# Power-PCB.net
KiCad netlist of a schematic drawn in EAGLE
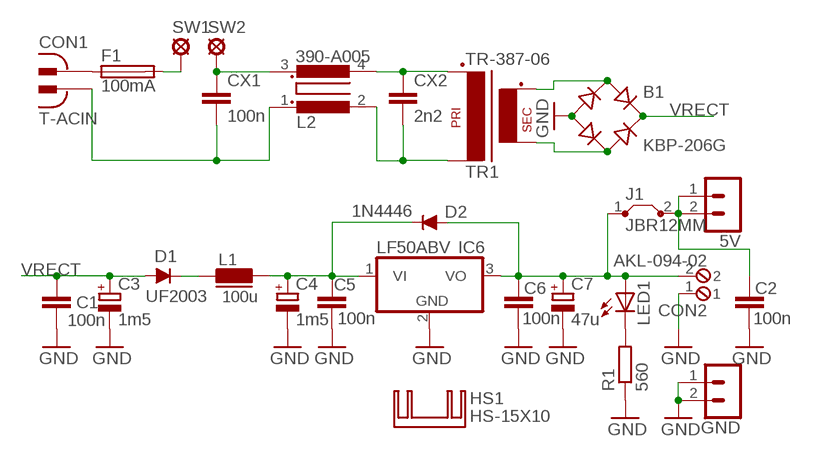
[diagram p0: schematic, sheet 1]

(export (version "E")
  (design (tool "Eeschema 10.0.6"))
  (components
    (comp (ref "5V")
      (value "MA02-1")
      (footprint "eagle-import:MA02-1")
      (libsource (lib "eagle-import") (part "MA02-1"))
    )
    (comp (ref "B1")
      (value "KBP-206G")
      (footprint "eagle-import:2KBP")
      (libsource (lib "eagle-import") (part "RECTIFIER-2KBP"))
    )
    (comp (ref "C1")
      (value "100n")
      (footprint "eagle-import:C050-024X044")
      (libsource (lib "eagle-import") (part "C-EU050-024X044"))
    )
    (comp (ref "C2")
      (value "100n")
      (footprint "eagle-import:C050-024X044")
      (libsource (lib "eagle-import") (part "C-EU050-024X044"))
    )
    (comp (ref "C3")
      (value "1m5")
      (footprint "eagle-import:E5-10,5")
      (libsource (lib "eagle-import") (part "CPOL-EUE5-10.5"))
    )
    (comp (ref "C4")
      (value "1m5")
      (footprint "eagle-import:E5-10,5")
      (libsource (lib "eagle-import") (part "CPOL-EUE5-10.5"))
    )
    (comp (ref "C5")
      (value "100n")
      (footprint "eagle-import:C050-024X044")
      (libsource (lib "eagle-import") (part "C-EU050-024X044"))
    )
    (comp (ref "C6")
      (value "100n")
      (footprint "eagle-import:C050-024X044")
      (libsource (lib "eagle-import") (part "C-EU050-024X044"))
    )
    (comp (ref "C7")
      (value "47u")
      (footprint "eagle-import:E2,5-6")
      (libsource (lib "eagle-import") (part "CPOL-EUE2.5-6"))
    )
    (comp (ref "CON1")
      (value "T-ACIN")
      (footprint "eagle-import:TECHNICS-ACIN1")
      (libsource (lib "eagle-import") (part "T-ACIN"))
    )
    (comp (ref "CON2")
      (value "AKL-094-02")
      (footprint "eagle-import:AKL-094-02")
      (libsource (lib "eagle-import") (part "AKL-094-02"))
    )
    (comp (ref "CX1")
      (value "100n")
      (footprint "eagle-import:XC15B6")
      (libsource (lib "eagle-import") (part "CXXC15B6"))
    )
    (comp (ref "CX2")
      (value "2n2")
      (footprint "eagle-import:C075-032X103")
      (libsource (lib "eagle-import") (part "C-EU075-032X103"))
    )
    (comp (ref "D1")
      (value "UF2003")
      (footprint "eagle-import:DO41-10A")
      (libsource (lib "eagle-import") (part "DIODE-DO41-10A"))
    )
    (comp (ref "D2")
      (value "1N4446")
      (footprint "eagle-import:DO35-10")
      (libsource (lib "eagle-import") (part "1N4446"))
    )
    (comp (ref "F1")
      (value "100mA")
      (footprint "eagle-import:KS9V")
      (libsource (lib "eagle-import") (part "FUSEKS9V"))
    )
    (comp (ref "GND")
      (value "MA02-1")
      (footprint "eagle-import:MA02-1")
      (libsource (lib "eagle-import") (part "MA02-1"))
    )
    (comp (ref "HS1")
      (value "HS-15X10")
      (footprint "eagle-import:HEATSINK-TO220-15X10X21")
      (libsource (lib "eagle-import") (part "HS-15X10"))
    )
    (comp (ref "IC6")
      (value "LF50ABV")
      (footprint "eagle-import:TO220V")
      (libsource (lib "eagle-import") (part "78TV05"))
    )
    (comp (ref "J1")
      (value "JBR12MM")
      (footprint "eagle-import:12-THICK-WIRE")
      (libsource (lib "eagle-import") (part "JUMPER-BRIGDE12MM"))
    )
    (comp (ref "L1")
      (value "100u")
      (footprint "eagle-import:07HCP")
      (libsource (lib "eagle-import") (part "07HCP"))
    )
    (comp (ref "L2")
      (value "390-A005")
      (footprint "eagle-import:390-A005")
      (libsource (lib "eagle-import") (part "390-A005"))
    )
    (comp (ref "LED1")
      (value "LED5MM")
      (footprint "eagle-import:LED5MM")
      (libsource (lib "eagle-import") (part "LED5MM"))
    )
    (comp (ref "R1")
      (value "560")
      (footprint "eagle-import:0207_10")
      (libsource (lib "eagle-import") (part "R-EU_0207/10"))
    )
    (comp (ref "SW1")
      (value "SE13")
      (footprint "eagle-import:SE13")
      (libsource (lib "eagle-import") (part "SE13"))
    )
    (comp (ref "SW2")
      (value "SE13")
      (footprint "eagle-import:SE13")
      (libsource (lib "eagle-import") (part "SE13"))
    )
    (comp (ref "TR1")
      (value "TR-387-06")
      (footprint "eagle-import:TRAFO-GERTH-387-06")
      (libsource (lib "eagle-import") (part "TR-387-06"))
    )
  )
  (nets
    (net (code "1") (name "/VRECT") (class "Default")
      (node (ref "B1") (pin "+") (pinfunction "+_+") (pintype "passive"))
      (node (ref "C1") (pin "1") (pinfunction "1_1") (pintype "passive"))
      (node (ref "C3") (pin "+") (pinfunction "+_+") (pintype "passive"))
      (node (ref "D1") (pin "A") (pinfunction "A_A") (pintype "passive"))
    )
    (net (code "2") (name "GND") (class "Default")
      (node (ref "B1") (pin "-") (pinfunction "-_-") (pintype "passive"))
      (node (ref "C1") (pin "2") (pinfunction "2_2") (pintype "passive"))
      (node (ref "C2") (pin "2") (pinfunction "2_2") (pintype "passive"))
      (node (ref "C3") (pin "-") (pinfunction "-_-") (pintype "passive"))
      (node (ref "C4") (pin "-") (pinfunction "-_-") (pintype "passive"))
      (node (ref "C5") (pin "2") (pinfunction "2_2") (pintype "passive"))
      (node (ref "C6") (pin "2") (pinfunction "2_2") (pintype "passive"))
      (node (ref "C7") (pin "-") (pinfunction "-_-") (pintype "passive"))
      (node (ref "CON2") (pin "1") (pinfunction "1_1") (pintype "passive"))
      (node (ref "GND") (pin "1") (pinfunction "1_1") (pintype "passive"))
      (node (ref "GND") (pin "2") (pinfunction "2_2") (pintype "passive"))
      (node (ref "IC6") (pin "2") (pinfunction "GND_2") (pintype "passive"))
      (node (ref "R1") (pin "1") (pinfunction "1_1") (pintype "passive"))
    )
    (net (code "3") (name "Net-(5V-Pad1)") (class "Default")
      (node (ref "5V") (pin "1") (pinfunction "1_1") (pintype "passive"))
      (node (ref "5V") (pin "2") (pinfunction "2_2") (pintype "passive"))
      (node (ref "C2") (pin "1") (pinfunction "1_1") (pintype "passive"))
      (node (ref "J1") (pin "2") (pinfunction "2_2") (pintype "passive"))
    )
    (net (code "4") (name "Net-(B1-PadAC1)") (class "Default")
      (node (ref "B1") (pin "AC1") (pinfunction "AC1_AC1") (pintype "passive"))
      (node (ref "TR1") (pin "S2") (pinfunction "S2_S2") (pintype "passive"))
    )
    (net (code "5") (name "Net-(B1-PadAC2)") (class "Default")
      (node (ref "B1") (pin "AC2") (pinfunction "AC2_AC2") (pintype "passive"))
      (node (ref "TR1") (pin "S1") (pinfunction "S1_S1") (pintype "passive"))
    )
    (net (code "6") (name "Net-(CON1-Pad1)") (class "Default")
      (node (ref "CON1") (pin "1") (pinfunction "1_1") (pintype "passive"))
      (node (ref "F1") (pin "1") (pinfunction "1_1") (pintype "passive"))
    )
    (net (code "7") (name "Net-(CON1-Pad2)") (class "Default")
      (node (ref "CON1") (pin "2") (pinfunction "2_2") (pintype "passive"))
      (node (ref "CX1") (pin "2") (pinfunction "2_2") (pintype "passive"))
      (node (ref "L2") (pin "1") (pinfunction "1_1") (pintype "passive"))
    )
    (net (code "8") (name "Net-(CX1-Pad1)") (class "Default")
      (node (ref "CX1") (pin "1") (pinfunction "1_1") (pintype "passive"))
      (node (ref "L2") (pin "3") (pinfunction "3_3") (pintype "passive"))
      (node (ref "SW2") (pin "MP") (pinfunction "MP_MP") (pintype "passive"))
    )
    (net (code "9") (name "Net-(CX2-Pad1)") (class "Default")
      (node (ref "CX2") (pin "1") (pinfunction "1_1") (pintype "passive"))
      (node (ref "L2") (pin "4") (pinfunction "4_4") (pintype "passive"))
      (node (ref "TR1") (pin "P2") (pinfunction "P2_P2") (pintype "passive"))
    )
    (net (code "10") (name "Net-(CX2-Pad2)") (class "Default")
      (node (ref "CX2") (pin "2") (pinfunction "2_2") (pintype "passive"))
      (node (ref "L2") (pin "2") (pinfunction "2_2") (pintype "passive"))
      (node (ref "TR1") (pin "P1") (pinfunction "P1_P1") (pintype "passive"))
    )
    (net (code "11") (name "Net-(D1-PadC)") (class "Default")
      (node (ref "D1") (pin "C") (pinfunction "C_C") (pintype "passive"))
      (node (ref "L1") (pin "1") (pinfunction "1_1") (pintype "passive"))
    )
    (net (code "12") (name "Net-(F1-Pad2)") (class "Default")
      (node (ref "F1") (pin "2") (pinfunction "2_2") (pintype "passive"))
      (node (ref "SW1") (pin "MP") (pinfunction "MP_MP") (pintype "passive"))
    )
    (net (code "13") (name "Net-(IC6-VI)") (class "Default")
      (node (ref "C4") (pin "+") (pinfunction "+_+") (pintype "passive"))
      (node (ref "C5") (pin "1") (pinfunction "1_1") (pintype "passive"))
      (node (ref "D2") (pin "C") (pinfunction "C_C") (pintype "passive"))
      (node (ref "IC6") (pin "1") (pinfunction "VI_1") (pintype "input"))
      (node (ref "L1") (pin "2") (pinfunction "2_2") (pintype "passive"))
    )
    (net (code "14") (name "Net-(IC6-VO)") (class "Default")
      (node (ref "C6") (pin "1") (pinfunction "1_1") (pintype "passive"))
      (node (ref "C7") (pin "+") (pinfunction "+_+") (pintype "passive"))
      (node (ref "CON2") (pin "2") (pinfunction "2_2") (pintype "passive"))
      (node (ref "D2") (pin "A") (pinfunction "A_A") (pintype "passive"))
      (node (ref "IC6") (pin "3") (pinfunction "VO_3") (pintype "passive"))
      (node (ref "J1") (pin "1") (pinfunction "1_1") (pintype "passive"))
      (node (ref "LED1") (pin "A") (pinfunction "A_A") (pintype "passive"))
    )
    (net (code "15") (name "Net-(LED1-C)") (class "Default")
      (node (ref "LED1") (pin "K") (pinfunction "C_K") (pintype "passive"))
      (node (ref "R1") (pin "2") (pinfunction "2_2") (pintype "passive"))
    )
  )
)
